# ext_bootload_activation.net
KiCad netlist of a schematic drawn in Altium Designer
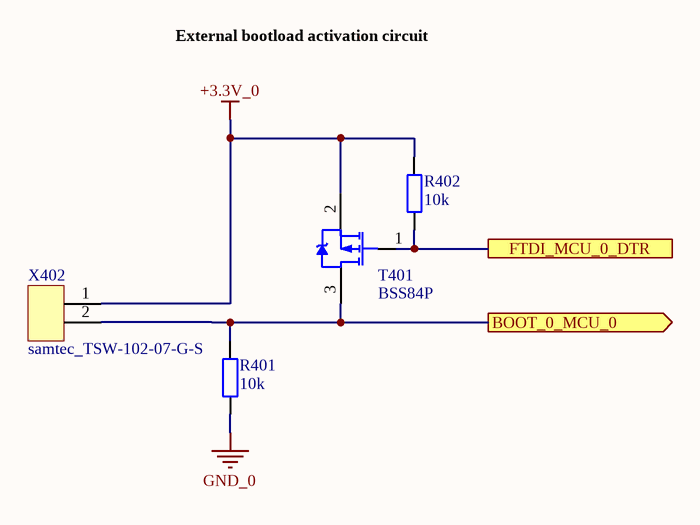
[diagram p0: ext_bootload_activation.SchDoc]

(export (version "E")
  (design (tool "Eeschema 10.0.6"))
  (components
    (comp (ref "R401")
      (value "10k")
      (footprint "RESC1608X05N")
      (description "SMD Resistor 10k 0603")
      (fields (field (name "PART NUMBER") "gen_R_10k_0603") (field (name "TOLERANCE") "1%"))
      (libsource (lib "OE750") (part "R"))
    )
    (comp (ref "R402")
      (value "10k")
      (footprint "RESC1608X05N")
      (description "SMD Resistor 10k 0603")
      (fields (field (name "PART NUMBER") "gen_R_10k_0603") (field (name "TOLERANCE") "1%"))
      (libsource (lib "OE750") (part "R"))
    )
    (comp (ref "T401")
      (value "BSS84P")
      (footprint "INF-PG-SOT23_N")
      (fields (field (name "MANUFACTURER") "Infineon"))
      (libsource (lib "Altium Content Vault") (part "INF-PEMOS-GSD-3-B"))
    )
    (comp (ref "X402")
      (value "samtec_TSW-102-07-G-S")
      (footprint "Pinheader_2.54_2")
      (description "Board-To-Board Connector, Vertical, 2.54 mm, 2 Contacts, Header, TSW Series, Through Hole, 1 Row")
      (fields (field (name "MANUFACTURER") "Samtec"))
      (libsource (lib "OE750") (part "X2"))
    )
  )
  (nets
    (net (code "1") (name "+3.3V_0") (class "Default")
      (node (ref "R402") (pin "2") (pinfunction "2_2") (pintype "passive"))
      (node (ref "T401") (pin "2") (pinfunction "SOURCE_2") (pintype "passive"))
      (node (ref "X402") (pin "1") (pintype "passive"))
    )
    (net (code "2") (name "/BOOT_0_MCU_0") (class "Default")
      (node (ref "R401") (pin "2") (pinfunction "2_2") (pintype "passive"))
      (node (ref "T401") (pin "3") (pinfunction "DRAIN_3") (pintype "passive"))
      (node (ref "X402") (pin "2") (pintype "passive"))
    )
    (net (code "3") (name "/FTDI_MCU_0_DTR") (class "Default")
      (node (ref "R402") (pin "1") (pinfunction "1_1") (pintype "passive"))
      (node (ref "T401") (pin "1") (pinfunction "GATE_1") (pintype "passive"))
    )
    (net (code "4") (name "GND_0") (class "Default")
      (node (ref "R401") (pin "1") (pinfunction "1_1") (pintype "passive"))
    )
  )
)
